# MiniAir724UG.net
KiCad netlist of a schematic drawn in Altium Designer
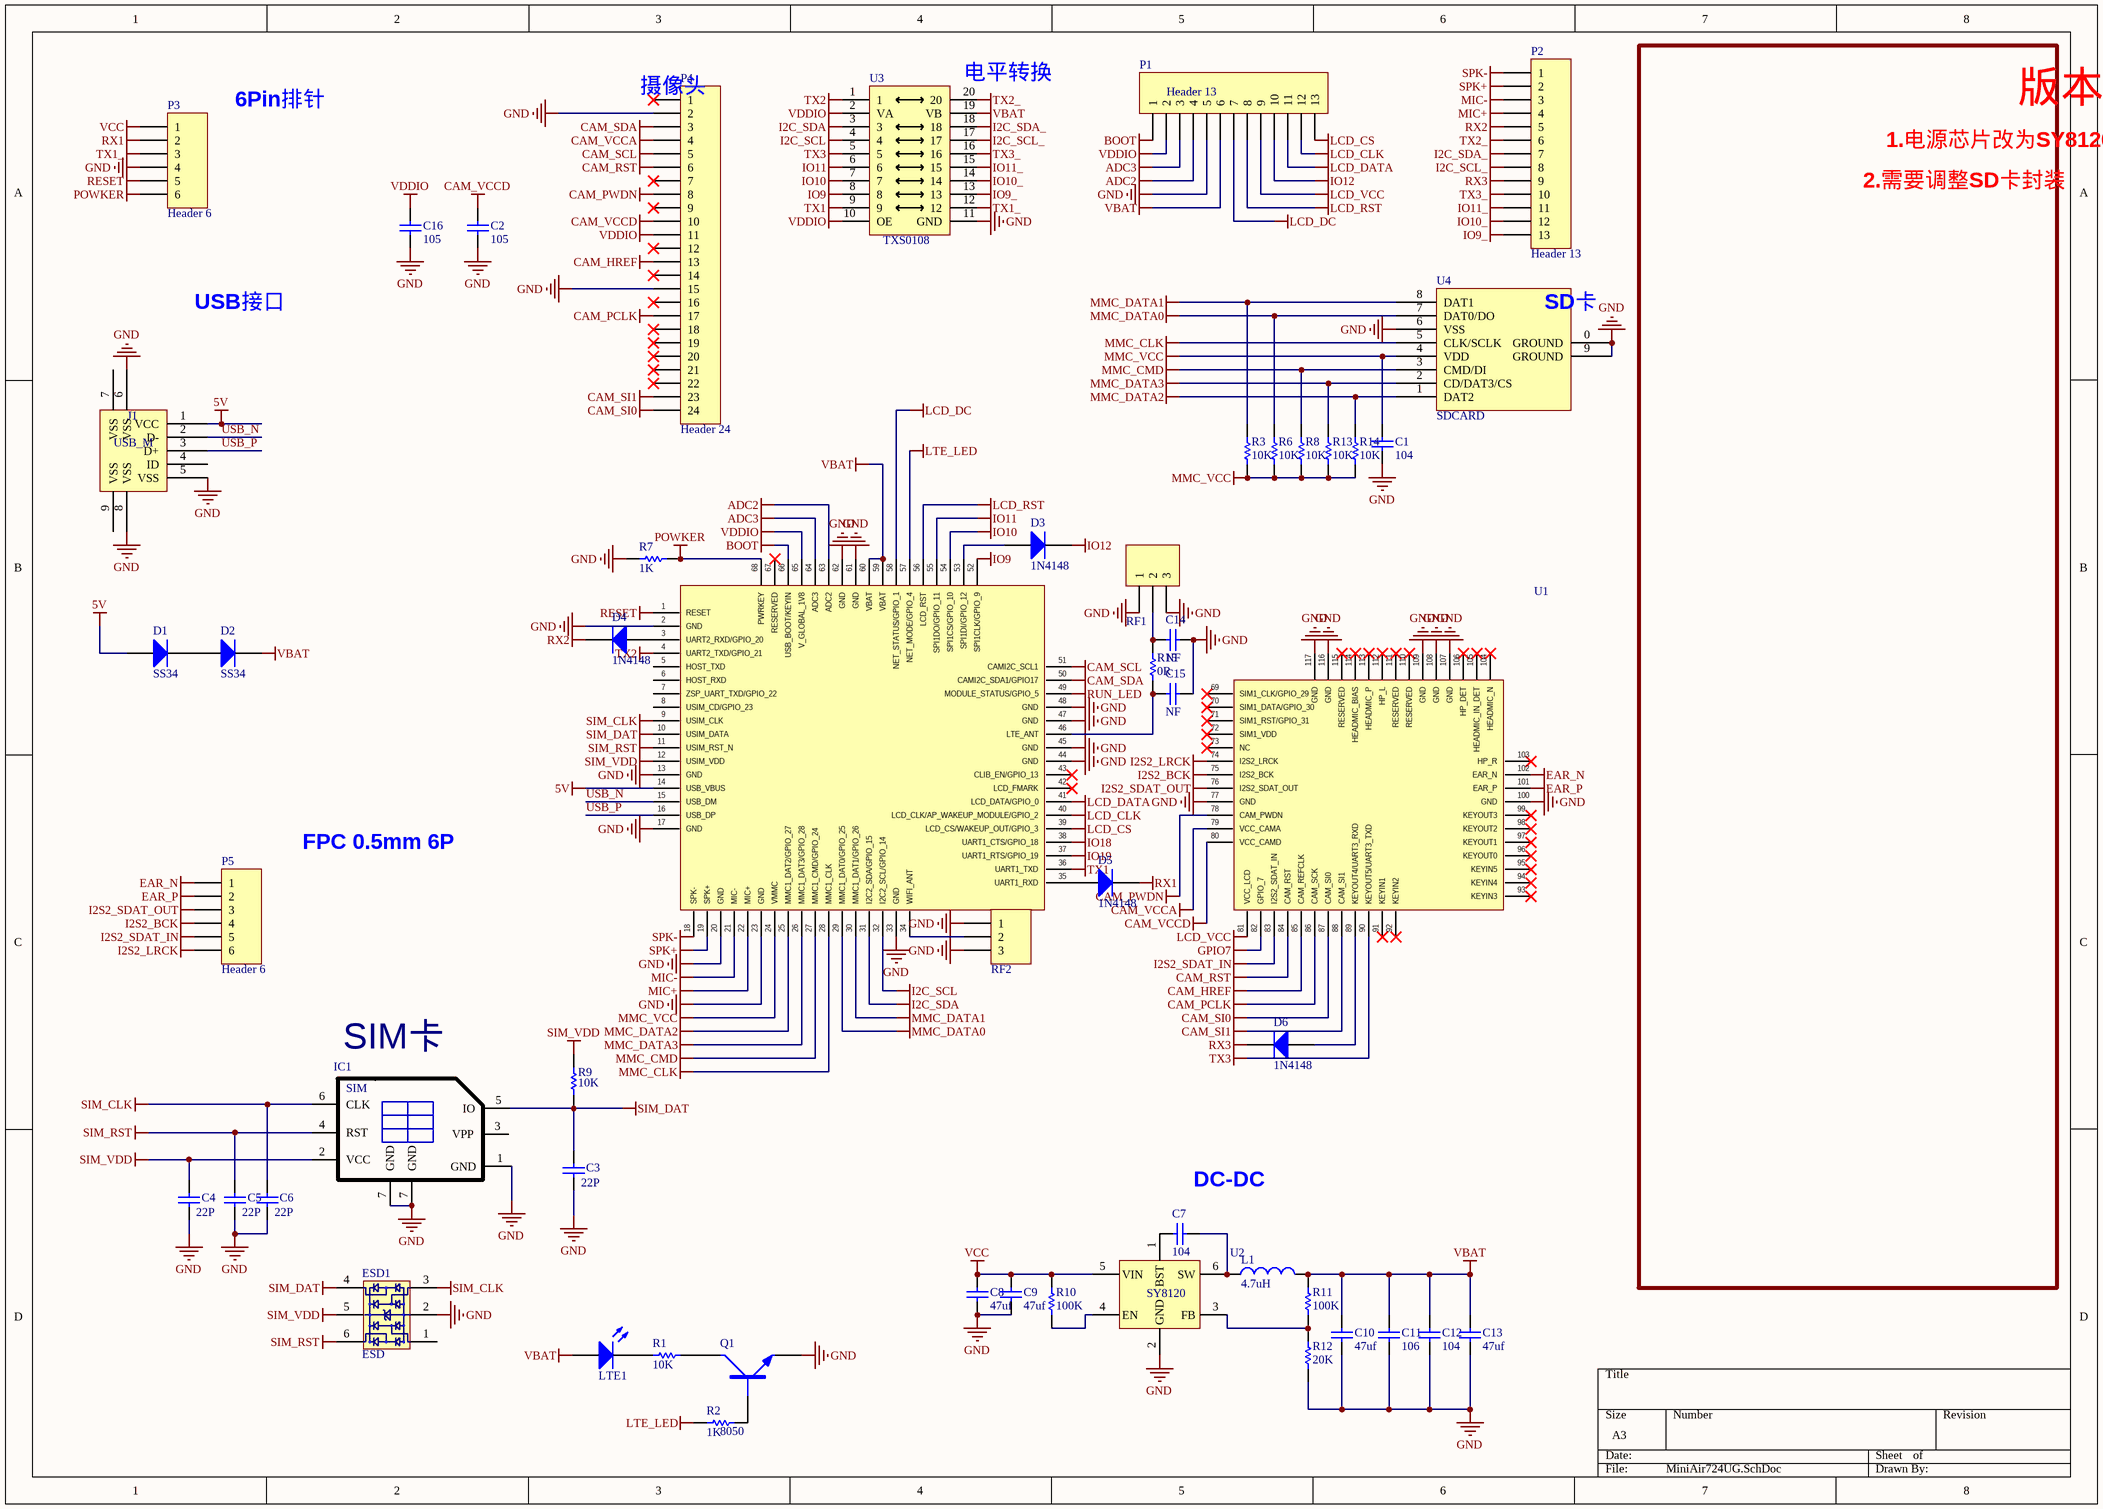
[diagram p0: MiniAir724UG.SchDoc]

(export (version "E")
  (design (tool "Eeschema 10.0.6"))
  (components
    (comp (ref "C1")
      (value "104")
      (footprint "0402C")
      (description "Capacitor")
      (fields (field (name "PUBLISHER") "Altium Limited"))
      (libsource (lib "Miscellaneous Devices") (part "Cap"))
    )
    (comp (ref "C2")
      (value "105")
      (footprint "0402C")
      (description "Capacitor")
      (fields (field (name "PUBLISHER") "Altium Limited"))
      (libsource (lib "Miscellaneous Devices") (part "Cap"))
    )
    (comp (ref "C3")
      (value "22P")
      (footprint "0402C")
      (description "Capacitor")
      (fields (field (name "PUBLISHER") "Altium Limited"))
      (libsource (lib "Miscellaneous Devices") (part "Cap"))
    )
    (comp (ref "C4")
      (value "22P")
      (footprint "0402C")
      (description "Capacitor")
      (fields (field (name "PUBLISHER") "Altium Limited"))
      (libsource (lib "Miscellaneous Devices") (part "Cap"))
    )
    (comp (ref "C5")
      (value "22P")
      (footprint "0402C")
      (description "Capacitor")
      (fields (field (name "PUBLISHER") "Altium Limited"))
      (libsource (lib "Miscellaneous Devices") (part "Cap"))
    )
    (comp (ref "C6")
      (value "22P")
      (footprint "0402C")
      (description "Capacitor")
      (fields (field (name "PUBLISHER") "Altium Limited"))
      (libsource (lib "Miscellaneous Devices") (part "Cap"))
    )
    (comp (ref "C7")
      (value "104")
      (footprint "0603C")
      (description "Capacitor")
      (fields (field (name "PUBLISHER") "Altium Limited"))
      (libsource (lib "Miscellaneous Devices") (part "Cap"))
    )
    (comp (ref "C8")
      (value "47uf")
      (footprint "1206C")
      (description "Capacitor")
      (fields (field (name "PUBLISHER") "Altium Limited"))
      (libsource (lib "Miscellaneous Devices") (part "Cap"))
    )
    (comp (ref "C9")
      (value "47uf")
      (footprint "1206C")
      (description "Capacitor")
      (fields (field (name "PUBLISHER") "Altium Limited"))
      (libsource (lib "Miscellaneous Devices") (part "Cap"))
    )
    (comp (ref "C10")
      (value "47uf")
      (footprint "1206C")
      (description "Capacitor")
      (fields (field (name "PUBLISHER") "Altium Limited"))
      (libsource (lib "Miscellaneous Devices") (part "Cap"))
    )
    (comp (ref "C11")
      (value "106")
      (footprint "0603C")
      (description "Capacitor")
      (fields (field (name "PUBLISHER") "Altium Limited"))
      (libsource (lib "Miscellaneous Devices") (part "Cap"))
    )
    (comp (ref "C12")
      (value "104")
      (footprint "0603C")
      (description "Capacitor")
      (fields (field (name "PUBLISHER") "Altium Limited"))
      (libsource (lib "Miscellaneous Devices") (part "Cap"))
    )
    (comp (ref "C13")
      (value "47uf")
      (footprint "1206C")
      (description "Capacitor")
      (fields (field (name "PUBLISHER") "Altium Limited"))
      (libsource (lib "Miscellaneous Devices") (part "Cap"))
    )
    (comp (ref "C14")
      (value "NF")
      (footprint "0603C")
      (description "Capacitor")
      (fields (field (name "PUBLISHER") "Altium Limited"))
      (libsource (lib "Miscellaneous Devices") (part "Cap"))
    )
    (comp (ref "C15")
      (value "NF")
      (footprint "0603C")
      (description "Capacitor")
      (fields (field (name "PUBLISHER") "Altium Limited"))
      (libsource (lib "Miscellaneous Devices") (part "Cap"))
    )
    (comp (ref "C16")
      (value "105")
      (footprint "0402C")
      (description "Capacitor")
      (fields (field (name "PUBLISHER") "Altium Limited"))
      (libsource (lib "Miscellaneous Devices") (part "Cap"))
    )
    (comp (ref "D1")
      (value "SS34")
      (footprint "SMA")
      (description "二极管")
      (fields (field (name "PUBLISHER") "Altium Limited"))
      (libsource (lib "Miscellaneous Devices") (part "Diode"))
    )
    (comp (ref "D2")
      (value "SS34")
      (footprint "SMA")
      (description "二极管")
      (fields (field (name "PUBLISHER") "Altium Limited"))
      (libsource (lib "Miscellaneous Devices") (part "Diode"))
    )
    (comp (ref "D3")
      (value "1N4148")
      (footprint "SOD-523")
      (description "快速二极管")
      (fields (field (name "PUBLISHER") "Altium Limited"))
      (libsource (lib "Miscellaneous Devices") (part "Diode"))
    )
    (comp (ref "D4")
      (value "1N4148")
      (footprint "SOD-523")
      (description "快速二极管")
      (fields (field (name "PUBLISHER") "Altium Limited"))
      (libsource (lib "Miscellaneous Devices") (part "Diode"))
    )
    (comp (ref "D5")
      (value "1N4148")
      (footprint "SOD-523")
      (description "快速二极管")
      (fields (field (name "PUBLISHER") "Altium Limited"))
      (libsource (lib "Miscellaneous Devices") (part "Diode"))
    )
    (comp (ref "D6")
      (value "1N4148")
      (footprint "SOD-523")
      (description "快速二极管")
      (fields (field (name "PUBLISHER") "Altium Limited"))
      (libsource (lib "Miscellaneous Devices") (part "Diode"))
    )
    (comp (ref "ESD1") (value "ESD") (footprint "PcbLib:SOT-236") (libsource (lib "fszhang") (part "ESD_4A")))
    (comp (ref "IC1") (value "SIM") (footprint "SIM-Nano") (libsource (lib "air202lib") (part "SIM")))
    (comp (ref "J1")
      (value "USB_M")
      (footprint "micro_usb_b")
      (description "MicroUSB接口")
      (libsource (lib "SchLib") (part "USB_M"))
    )
    (comp (ref "L1")
      (value "4.7uH")
      (footprint "SWPA4020S")
      (description "电感SLF7032")
      (fields (field (name "PUBLISHER") "Altium Limited"))
      (libsource (lib "Miscellaneous Devices") (part "Inductor"))
    )
    (comp (ref "LTE1")
      (value "LED")
      (footprint "0603LED")
      (description "Typical RED, GREEN, YELLOW, AMBER GaAs LED")
      (fields (field (name "PUBLISHER") "Altium Limited"))
      (libsource (lib "Miscellaneous Devices") (part "LED2"))
    )
    (comp (ref "P1")
      (value "Header 13")
      (footprint "HDR1X13")
      (description "Header, 13-Pin")
      (fields (field (name "PUBLISHER") "Altium Limited"))
      (libsource (lib "") (part "Header 13_1"))
    )
    (comp (ref "P2")
      (value "Header 13")
      (footprint "HDR1X13")
      (description "Header, 13-Pin")
      (fields (field (name "PUBLISHER") "Altium Limited"))
      (libsource (lib "Miscellaneous Connectors") (part "Header 13"))
    )
    (comp (ref "P3")
      (value "Header 6")
      (footprint "HDR1X6")
      (description "Header, 6-Pin")
      (fields (field (name "PUBLISHER") "Altium Limited"))
      (libsource (lib "Miscellaneous Connectors") (part "Header 6"))
    )
    (comp (ref "P4")
      (value "Header 24")
      (footprint "FPC0.5 2H-WS-24P")
      (description "Header, 24-Pin")
      (fields (field (name "PUBLISHER") "Altium Limited"))
      (libsource (lib "Miscellaneous Connectors") (part "Header 24"))
    )
    (comp (ref "P5")
      (value "Header 6")
      (footprint "FPC0.5 2H-WS-6P")
      (description "Header, 6-Pin")
      (fields (field (name "PUBLISHER") "Altium Limited"))
      (libsource (lib "Miscellaneous Connectors") (part "Header 6"))
    )
    (comp (ref "Q1") (value "8050") (footprint "SOT-23") (libsource (lib "32无线") (part "NPN")))
    (comp (ref "R1")
      (value "10K")
      (footprint "0402R")
      (description "Resistor")
      (fields (field (name "PUBLISHER") "Altium Limited"))
      (libsource (lib "Miscellaneous Devices") (part "Res1"))
    )
    (comp (ref "R2")
      (value "1K")
      (footprint "0402R")
      (description "Resistor")
      (fields (field (name "PUBLISHER") "Altium Limited"))
      (libsource (lib "Miscellaneous Devices") (part "Res1"))
    )
    (comp (ref "R3")
      (value "10K")
      (footprint "0402R")
      (description "Resistor")
      (fields (field (name "PUBLISHER") "Altium Limited"))
      (libsource (lib "Miscellaneous Devices") (part "Res1"))
    )
    (comp (ref "R6")
      (value "10K")
      (footprint "0402R")
      (description "Resistor")
      (fields (field (name "PUBLISHER") "Altium Limited"))
      (libsource (lib "Miscellaneous Devices") (part "Res1"))
    )
    (comp (ref "R7")
      (value "1K")
      (footprint "0402R")
      (description "Resistor")
      (fields (field (name "PUBLISHER") "Altium Limited"))
      (libsource (lib "Miscellaneous Devices") (part "Res1"))
    )
    (comp (ref "R8")
      (value "10K")
      (footprint "0402R")
      (description "Resistor")
      (fields (field (name "PUBLISHER") "Altium Limited"))
      (libsource (lib "Miscellaneous Devices") (part "Res1"))
    )
    (comp (ref "R9")
      (value "10K")
      (footprint "0402R")
      (description "Resistor")
      (fields (field (name "PUBLISHER") "Altium Limited"))
      (libsource (lib "Miscellaneous Devices") (part "Res1"))
    )
    (comp (ref "R10")
      (value "100K")
      (footprint "0603R")
      (description "Resistor")
      (fields (field (name "PUBLISHER") "Altium Limited"))
      (libsource (lib "Miscellaneous Devices") (part "Res1"))
    )
    (comp (ref "R11")
      (value "100K")
      (footprint "0603R")
      (description "Resistor")
      (fields (field (name "PUBLISHER") "Altium Limited"))
      (libsource (lib "Miscellaneous Devices") (part "Res1"))
    )
    (comp (ref "R12")
      (value "20K")
      (footprint "0603R")
      (description "Resistor")
      (fields (field (name "PUBLISHER") "Altium Limited"))
      (libsource (lib "Miscellaneous Devices") (part "Res1"))
    )
    (comp (ref "R13")
      (value "10K")
      (footprint "0402R")
      (description "Resistor")
      (fields (field (name "PUBLISHER") "Altium Limited"))
      (libsource (lib "Miscellaneous Devices") (part "Res1"))
    )
    (comp (ref "R14")
      (value "10K")
      (footprint "0402R")
      (description "Resistor")
      (fields (field (name "PUBLISHER") "Altium Limited"))
      (libsource (lib "Miscellaneous Devices") (part "Res1"))
    )
    (comp (ref "R15")
      (value "0R")
      (footprint "0603R")
      (description "Resistor")
      (fields (field (name "PUBLISHER") "Altium Limited"))
      (libsource (lib "Miscellaneous Devices") (part "Res1"))
    )
    (comp (ref "RF1")
      (value "Header 3")
      (footprint "IPEX")
      (description "接插件")
      (fields (field (name "PUBLISHER") "Altium Limited"))
      (libsource (lib "fszhang") (part "Header 3"))
    )
    (comp (ref "RF2")
      (value "Header 3")
      (footprint "IPEX")
      (description "接插件")
      (fields (field (name "PUBLISHER") "Altium Limited"))
      (libsource (lib "") (part "Header 3_1"))
    )
    (comp (ref "U1")
      (value "Air724")
      (footprint "AIR724UG")
      (fields (field (name "PUBLISHER") "Altium Limited"))
      (libsource (lib "SchLib") (part "Air724UG"))
    )
    (comp (ref "U2") (value "SY8120") (footprint "SOT-236") (libsource (lib "SchLib") (part "JW5026")))
    (comp (ref "U3") (value "TXS0108") (footprint "SSOP20") (libsource (lib "fszhang") (part "TXS0108")))
    (comp (ref "U4")
      (value "SDCARD")
      (footprint "SDCARD-Mini")
      (libsource (lib "SchLib") (part "SDCARD-Mini"))
    )
  )
  (nets
    (net (code "1") (name "/USB_N") (class "Default")
      (node (ref "J1") (pin "2") (pinfunction "D-_2") (pintype "passive"))
      (node (ref "U1") (pin "15") (pinfunction "USB_DM_15") (pintype "passive"))
    )
    (net (code "2") (name "/USB_P") (class "Default")
      (node (ref "J1") (pin "3") (pinfunction "D+_3") (pintype "passive"))
      (node (ref "U1") (pin "16") (pinfunction "USB_DP_16") (pintype "passive"))
    )
    (net (code "3") (name "5V") (class "Default")
      (node (ref "D1") (pin "1") (pinfunction "A_1") (pintype "passive"))
      (node (ref "J1") (pin "1") (pinfunction "VCC_1") (pintype "passive"))
      (node (ref "U1") (pin "14") (pinfunction "USB_VBUS_14") (pintype "passive"))
    )
    (net (code "4") (name "ADC2") (class "Default")
      (node (ref "P1") (pin "4") (pinfunction "4_4") (pintype "passive"))
      (node (ref "U1") (pin "63") (pinfunction "ADC2_63") (pintype "passive"))
    )
    (net (code "5") (name "ADC3") (class "Default")
      (node (ref "P1") (pin "3") (pinfunction "3_3") (pintype "passive"))
      (node (ref "U1") (pin "64") (pinfunction "ADC3_64") (pintype "passive"))
    )
    (net (code "6") (name "BOOT") (class "Default")
      (node (ref "P1") (pin "1") (pinfunction "1_1") (pintype "passive"))
      (node (ref "U1") (pin "66") (pinfunction "USB_BOOT/KEYIN_66") (pintype "passive"))
    )
    (net (code "7") (name "CAM_HREF") (class "Default")
      (node (ref "P4") (pin "13") (pinfunction "13_13") (pintype "passive"))
      (node (ref "U1") (pin "85") (pinfunction "CAM_REFCLK_85") (pintype "passive"))
    )
    (net (code "8") (name "CAM_PCLK") (class "Default")
      (node (ref "P4") (pin "17") (pinfunction "17_17") (pintype "passive"))
      (node (ref "U1") (pin "86") (pinfunction "CAM_SCK_86") (pintype "passive"))
    )
    (net (code "9") (name "CAM_PWDN") (class "Default")
      (node (ref "P4") (pin "8") (pinfunction "8_8") (pintype "passive"))
      (node (ref "U1") (pin "78") (pinfunction "CAM_PWDN_78") (pintype "passive"))
    )
    (net (code "10") (name "CAM_RST") (class "Default")
      (node (ref "P4") (pin "6") (pinfunction "6_6") (pintype "passive"))
      (node (ref "U1") (pin "84") (pinfunction "CAM_RST_84") (pintype "passive"))
    )
    (net (code "11") (name "CAM_SCL") (class "Default")
      (node (ref "P4") (pin "5") (pinfunction "5_5") (pintype "passive"))
      (node (ref "U1") (pin "51") (pinfunction "CAMI2C_SCL1_51") (pintype "passive"))
    )
    (net (code "12") (name "CAM_SDA") (class "Default")
      (node (ref "P4") (pin "3") (pinfunction "3_3") (pintype "passive"))
      (node (ref "U1") (pin "50") (pinfunction "CAMI2C_SDA1/GPIO17_50") (pintype "passive"))
    )
    (net (code "13") (name "CAM_SI0") (class "Default")
      (node (ref "P4") (pin "24") (pinfunction "24_24") (pintype "passive"))
      (node (ref "U1") (pin "87") (pinfunction "CAM_SI0_87") (pintype "passive"))
    )
    (net (code "14") (name "CAM_SI1") (class "Default")
      (node (ref "P4") (pin "23") (pinfunction "23_23") (pintype "passive"))
      (node (ref "U1") (pin "88") (pinfunction "CAM_SI1_88") (pintype "passive"))
    )
    (net (code "15") (name "CAM_VCCA") (class "Default")
      (node (ref "P4") (pin "4") (pinfunction "4_4") (pintype "passive"))
      (node (ref "U1") (pin "79") (pinfunction "VCC_CAMA_79") (pintype "passive"))
    )
    (net (code "16") (name "CAM_VCCD") (class "Default")
      (node (ref "C2") (pin "2") (pinfunction "2_2") (pintype "passive"))
      (node (ref "P4") (pin "10") (pinfunction "10_10") (pintype "passive"))
      (node (ref "U1") (pin "80") (pinfunction "VCC_CAMD_80") (pintype "passive"))
    )
    (net (code "17") (name "EAR_N") (class "Default")
      (node (ref "P5") (pin "1") (pinfunction "1_1") (pintype "passive"))
      (node (ref "U1") (pin "102") (pinfunction "EAR_N_102") (pintype "passive"))
    )
    (net (code "18") (name "EAR_P") (class "Default")
      (node (ref "P5") (pin "2") (pinfunction "2_2") (pintype "passive"))
      (node (ref "U1") (pin "101") (pinfunction "EAR_P_101") (pintype "passive"))
    )
    (net (code "19") (name "GND") (class "Default")
      (node (ref "C1") (pin "1") (pinfunction "1_1") (pintype "passive"))
      (node (ref "C10") (pin "1") (pinfunction "1_1") (pintype "passive"))
      (node (ref "C11") (pin "1") (pinfunction "1_1") (pintype "passive"))
      (node (ref "C12") (pin "1") (pinfunction "1_1") (pintype "passive"))
      (node (ref "C13") (pin "1") (pinfunction "1_1") (pintype "passive"))
      (node (ref "C14") (pin "1") (pinfunction "1_1") (pintype "passive"))
      (node (ref "C15") (pin "1") (pinfunction "1_1") (pintype "passive"))
      (node (ref "C16") (pin "1") (pinfunction "1_1") (pintype "passive"))
      (node (ref "C2") (pin "1") (pinfunction "1_1") (pintype "passive"))
      (node (ref "C3") (pin "2") (pinfunction "2_2") (pintype "passive"))
      (node (ref "C4") (pin "2") (pinfunction "2_2") (pintype "passive"))
      (node (ref "C5") (pin "2") (pinfunction "2_2") (pintype "passive"))
      (node (ref "C6") (pin "2") (pinfunction "2_2") (pintype "passive"))
      (node (ref "C8") (pin "1") (pinfunction "1_1") (pintype "passive"))
      (node (ref "C9") (pin "1") (pinfunction "1_1") (pintype "passive"))
      (node (ref "ESD1") (pin "2") (pinfunction "2_2") (pintype "passive"))
      (node (ref "IC1") (pin "1") (pinfunction "GND_1") (pintype "passive"))
      (node (ref "IC1") (pin "7") (pinfunction "GND_7") (pintype "passive"))
      (node (ref "J1") (pin "5") (pinfunction "VSS_5") (pintype "passive"))
      (node (ref "J1") (pin "6") (pinfunction "VSS_6") (pintype "passive"))
      (node (ref "J1") (pin "8") (pinfunction "VSS_8") (pintype "passive"))
      (node (ref "P1") (pin "5") (pinfunction "5_5") (pintype "passive"))
      (node (ref "P3") (pin "4") (pinfunction "4_4") (pintype "passive"))
      (node (ref "P4") (pin "15") (pinfunction "15_15") (pintype "passive"))
      (node (ref "P4") (pin "2") (pinfunction "2_2") (pintype "passive"))
      (node (ref "Q1") (pin "2") (pinfunction "E_2") (pintype "passive"))
      (node (ref "R12") (pin "1") (pinfunction "1_1") (pintype "passive"))
      (node (ref "R7") (pin "1") (pinfunction "1_1") (pintype "passive"))
      (node (ref "RF1") (pin "1") (pinfunction "1_1") (pintype "passive"))
      (node (ref "RF1") (pin "3") (pinfunction "3_3") (pintype "passive"))
      (node (ref "RF2") (pin "1") (pinfunction "1_1") (pintype "passive"))
      (node (ref "RF2") (pin "3") (pinfunction "3_3") (pintype "passive"))
      (node (ref "U1") (pin "100") (pinfunction "GND_100") (pintype "passive"))
      (node (ref "U1") (pin "107") (pinfunction "GND_107") (pintype "passive"))
      (node (ref "U1") (pin "108") (pinfunction "GND_108") (pintype "passive"))
      (node (ref "U1") (pin "109") (pinfunction "GND_109") (pintype "passive"))
      (node (ref "U1") (pin "116") (pinfunction "GND_116") (pintype "passive"))
      (node (ref "U1") (pin "117") (pinfunction "GND_117") (pintype "passive"))
      (node (ref "U1") (pin "13") (pinfunction "GND_13") (pintype "passive"))
      (node (ref "U1") (pin "17") (pinfunction "GND_17") (pintype "passive"))
      (node (ref "U1") (pin "2") (pinfunction "GND_2") (pintype "passive"))
      (node (ref "U1") (pin "20") (pinfunction "GND_20") (pintype "passive"))
      (node (ref "U1") (pin "23") (pinfunction "GND_23") (pintype "passive"))
      (node (ref "U1") (pin "33") (pinfunction "GND_33") (pintype "passive"))
      (node (ref "U1") (pin "44") (pinfunction "GND_44") (pintype "passive"))
      (node (ref "U1") (pin "45") (pinfunction "GND_45") (pintype "passive"))
      (node (ref "U1") (pin "47") (pinfunction "GND_47") (pintype "passive"))
      (node (ref "U1") (pin "48") (pinfunction "GND_48") (pintype "passive"))
      (node (ref "U1") (pin "61") (pinfunction "GND_61") (pintype "passive"))
      (node (ref "U1") (pin "62") (pinfunction "GND_62") (pintype "passive"))
      (node (ref "U1") (pin "77") (pinfunction "GND_77") (pintype "passive"))
      (node (ref "U2") (pin "2") (pinfunction "GND_2") (pintype "passive"))
      (node (ref "U3") (pin "11") (pinfunction "GND_11") (pintype "passive"))
      (node (ref "U4") (pin "0") (pinfunction "GROUND_0") (pintype "passive"))
      (node (ref "U4") (pin "6") (pinfunction "VSS_6") (pintype "passive"))
      (node (ref "U4") (pin "9") (pinfunction "GROUND_9") (pintype "passive"))
    )
    (net (code "20") (name "GPIO7") (class "Default")
      (node (ref "U1") (pin "82") (pinfunction "GPIO_7_82") (pintype "passive"))
    )
    (net (code "21") (name "I2C_SCL") (class "Default")
      (node (ref "U1") (pin "32") (pinfunction "I2C2_SCL/GPIO_14_32") (pintype "passive"))
      (node (ref "U3") (pin "4") (pinfunction "4_4") (pintype "passive"))
    )
    (net (code "22") (name "I2C_SCL_") (class "Default")
      (node (ref "P2") (pin "8") (pinfunction "8_8") (pintype "passive"))
      (node (ref "U3") (pin "17") (pinfunction "17_17") (pintype "passive"))
    )
    (net (code "23") (name "I2C_SDA") (class "Default")
      (node (ref "U1") (pin "31") (pinfunction "I2C2_SDA/GPIO_15_31") (pintype "passive"))
      (node (ref "U3") (pin "3") (pinfunction "3_3") (pintype "passive"))
    )
    (net (code "24") (name "I2C_SDA_") (class "Default")
      (node (ref "P2") (pin "7") (pinfunction "7_7") (pintype "passive"))
      (node (ref "U3") (pin "18") (pinfunction "18_18") (pintype "passive"))
    )
    (net (code "25") (name "I2S2_BCK") (class "Default")
      (node (ref "P5") (pin "4") (pinfunction "4_4") (pintype "passive"))
      (node (ref "U1") (pin "75") (pinfunction "I2S2_BCK_75") (pintype "passive"))
    )
    (net (code "26") (name "I2S2_LRCK") (class "Default")
      (node (ref "P5") (pin "6") (pinfunction "6_6") (pintype "passive"))
      (node (ref "U1") (pin "74") (pinfunction "I2S2_LRCK_74") (pintype "passive"))
    )
    (net (code "27") (name "I2S2_SDAT_IN") (class "Default")
      (node (ref "P5") (pin "5") (pinfunction "5_5") (pintype "passive"))
      (node (ref "U1") (pin "83") (pinfunction "I2S2_SDAT_IN_83") (pintype "passive"))
    )
    (net (code "28") (name "I2S2_SDAT_OUT") (class "Default")
      (node (ref "P5") (pin "3") (pinfunction "3_3") (pintype "passive"))
      (node (ref "U1") (pin "76") (pinfunction "I2S2_SDAT_OUT_76") (pintype "passive"))
    )
    (net (code "29") (name "IO9") (class "Default")
      (node (ref "U1") (pin "52") (pinfunction "SPI1CLK/GPIO_9_52") (pintype "passive"))
      (node (ref "U3") (pin "8") (pinfunction "8_8") (pintype "passive"))
    )
    (net (code "30") (name "IO9_") (class "Default")
      (node (ref "P2") (pin "13") (pinfunction "13_13") (pintype "passive"))
      (node (ref "U3") (pin "13") (pinfunction "13_13") (pintype "passive"))
    )
    (net (code "31") (name "IO10") (class "Default")
      (node (ref "U1") (pin "54") (pinfunction "SPI1CS/GPIO_10_54") (pintype "passive"))
      (node (ref "U3") (pin "7") (pinfunction "7_7") (pintype "passive"))
    )
    (net (code "32") (name "IO10_") (class "Default")
      (node (ref "P2") (pin "12") (pinfunction "12_12") (pintype "passive"))
      (node (ref "U3") (pin "14") (pinfunction "14_14") (pintype "passive"))
    )
    (net (code "33") (name "IO11") (class "Default")
      (node (ref "U1") (pin "55") (pinfunction "SPI1DO/GPIO_11_55") (pintype "passive"))
      (node (ref "U3") (pin "6") (pinfunction "6_6") (pintype "passive"))
    )
    (net (code "34") (name "IO11_") (class "Default")
      (node (ref "P2") (pin "11") (pinfunction "11_11") (pintype "passive"))
      (node (ref "U3") (pin "15") (pinfunction "15_15") (pintype "passive"))
    )
    (net (code "35") (name "IO12") (class "Default")
      (node (ref "D3") (pin "2") (pinfunction "K_2") (pintype "passive"))
      (node (ref "P1") (pin "10") (pinfunction "10_10") (pintype "passive"))
    )
    (net (code "36") (name "IO18") (class "Default")
      (node (ref "U1") (pin "38") (pinfunction "UART1_CTS/GPIO_18_38") (pintype "passive"))
    )
    (net (code "37") (name "IO19") (class "Default")
      (node (ref "U1") (pin "37") (pinfunction "UART1_RTS/GPIO_19_37") (pintype "passive"))
    )
    (net (code "38") (name "LCD_CLK") (class "Default")
      (node (ref "P1") (pin "12") (pinfunction "12_12") (pintype "passive"))
      (node (ref "U1") (pin "40") (pinfunction "LCD_CLK/AP_WAKEUP_MODULE/GPIO_2_40") (pintype "passive"))
    )
    (net (code "39") (name "LCD_CS") (class "Default")
      (node (ref "P1") (pin "13") (pinfunction "13_13") (pintype "passive"))
      (node (ref "U1") (pin "39") (pinfunction "LCD_CS/WAKEUP_OUT/GPIO_3_39") (pintype "passive"))
    )
    (net (code "40") (name "LCD_DATA") (class "Default")
      (node (ref "P1") (pin "11") (pinfunction "11_11") (pintype "passive"))
      (node (ref "U1") (pin "41") (pinfunction "LCD_DATA/GPIO_0_41") (pintype "passive"))
    )
    (net (code "41") (name "LCD_DC") (class "Default")
      (node (ref "P1") (pin "7") (pinfunction "7_7") (pintype "passive"))
      (node (ref "U1") (pin "58") (pinfunction "NET_STATUS/GPIO_1_58") (pintype "passive"))
    )
    (net (code "42") (name "LCD_RST") (class "Default")
      (node (ref "P1") (pin "8") (pinfunction "8_8") (pintype "passive"))
      (node (ref "U1") (pin "56") (pinfunction "LCD_RST_56") (pintype "passive"))
    )
    (net (code "43") (name "LCD_VCC") (class "Default")
      (node (ref "P1") (pin "9") (pinfunction "9_9") (pintype "passive"))
      (node (ref "U1") (pin "81") (pinfunction "VCC_LCD_81") (pintype "passive"))
    )
    (net (code "44") (name "LTE_LED") (class "Default")
      (node (ref "R2") (pin "2") (pinfunction "2_2") (pintype "passive"))
      (node (ref "U1") (pin "57") (pinfunction "NET_MODE/GPIO_4_57") (pintype "passive"))
    )
    (net (code "45") (name "MIC+") (class "Default")
      (node (ref "P2") (pin "4") (pinfunction "4_4") (pintype "passive"))
      (node (ref "U1") (pin "22") (pinfunction "MIC+_22") (pintype "passive"))
    )
    (net (code "46") (name "MIC-") (class "Default")
      (node (ref "P2") (pin "3") (pinfunction "3_3") (pintype "passive"))
      (node (ref "U1") (pin "21") (pinfunction "MIC-_21") (pintype "passive"))
    )
    (net (code "47") (name "MMC_CLK") (class "Default")
      (node (ref "U1") (pin "28") (pinfunction "MMC1_CLK_28") (pintype "passive"))
      (node (ref "U4") (pin "5") (pinfunction "CLK/SCLK_5") (pintype "passive"))
    )
    (net (code "48") (name "MMC_CMD") (class "Default")
      (node (ref "R8") (pin "1") (pinfunction "1_1") (pintype "passive"))
      (node (ref "U1") (pin "27") (pinfunction "MMC1_CMD/GPIO_24_27") (pintype "passive"))
      (node (ref "U4") (pin "3") (pinfunction "CMD/DI_3") (pintype "passive"))
    )
    (net (code "49") (name "MMC_DATA0") (class "Default")
      (node (ref "R6") (pin "1") (pinfunction "1_1") (pintype "passive"))
      (node (ref "U1") (pin "29") (pinfunction "MMC1_DAT0/GPIO_25_29") (pintype "passive"))
      (node (ref "U4") (pin "7") (pinfunction "DAT0/DO_7") (pintype "passive"))
    )
    (net (code "50") (name "MMC_DATA1") (class "Default")
      (node (ref "R3") (pin "1") (pinfunction "1_1") (pintype "passive"))
      (node (ref "U1") (pin "30") (pinfunction "MMC1_DAT1/GPIO_26_30") (pintype "passive"))
      (node (ref "U4") (pin "8") (pinfunction "DAT1_8") (pintype "passive"))
    )
    (net (code "51") (name "MMC_DATA2") (class "Default")
      (node (ref "R14") (pin "1") (pinfunction "1_1") (pintype "passive"))
      (node (ref "U1") (pin "25") (pinfunction "MMC1_DAT2/GPIO_27_25") (pintype "passive"))
      (node (ref "U4") (pin "1") (pinfunction "DAT2_1") (pintype "passive"))
    )
    (net (code "52") (name "MMC_DATA3") (class "Default")
      (node (ref "R13") (pin "1") (pinfunction "1_1") (pintype "passive"))
      (node (ref "U1") (pin "26") (pinfunction "MMC1_DAT3/GPIO_28_26") (pintype "passive"))
      (node (ref "U4") (pin "2") (pinfunction "CD/DAT3/CS_2") (pintype "passive"))
    )
    (net (code "53") (name "MMC_VCC") (class "Default")
      (node (ref "C1") (pin "2") (pinfunction "2_2") (pintype "passive"))
      (node (ref "R13") (pin "2") (pinfunction "2_2") (pintype "passive"))
      (node (ref "R14") (pin "2") (pinfunction "2_2") (pintype "passive"))
      (node (ref "R3") (pin "2") (pinfunction "2_2") (pintype "passive"))
      (node (ref "R6") (pin "2") (pinfunction "2_2") (pintype "passive"))
      (node (ref "R8") (pin "2") (pinfunction "2_2") (pintype "passive"))
      (node (ref "U1") (pin "24") (pinfunction "VMMC_24") (pintype "passive"))
      (node (ref "U4") (pin "4") (pinfunction "VDD_4") (pintype "passive"))
    )
    (net (code "54") (name "Net-(C14-Pad2)") (class "Default")
      (node (ref "C14") (pin "2") (pinfunction "2_2") (pintype "passive"))
      (node (ref "R15") (pin "2") (pinfunction "2_2") (pintype "passive"))
      (node (ref "RF1") (pin "2") (pinfunction "2_2") (pintype "passive"))
    )
    (net (code "55") (name "Net-(D1-K)") (class "Default")
      (node (ref "D1") (pin "2") (pinfunction "K_2") (pintype "passive"))
      (node (ref "D2") (pin "1") (pinfunction "A_1") (pintype "passive"))
    )
    (net (code "56") (name "Net-(D3-A)") (class "Default")
      (node (ref "D3") (pin "1") (pinfunction "A_1") (pintype "passive"))
      (node (ref "U1") (pin "53") (pinfunction "SPI1DI/GPIO_12_53") (pintype "passive"))
    )
    (net (code "57") (name "Net-(D4-A)") (class "Default")
      (node (ref "D4") (pin "1") (pinfunction "A_1") (pintype "passive"))
      (node (ref "U1") (pin "3") (pinfunction "UART2_RXD/GPIO_20_3") (pintype "passive"))
    )
    (net (code "58") (name "Net-(D5-A)") (class "Default")
      (node (ref "D5") (pin "1") (pinfunction "A_1") (pintype "passive"))
      (node (ref "U1") (pin "35") (pinfunction "UART1_RXD_35") (pintype "passive"))
    )
    (net (code "59") (name "Net-(D6-A)") (class "Default")
      (node (ref "D6") (pin "1") (pinfunction "A_1") (pintype "passive"))
      (node (ref "U1") (pin "89") (pinfunction "KEYOUT4/UART3_RXD_89") (pintype "passive"))
    )
    (net (code "60") (name "Net-(LTE1-K)") (class "Default")
      (node (ref "LTE1") (pin "2") (pinfunction "K_2") (pintype "passive"))
      (node (ref "R1") (pin "2") (pinfunction "2_2") (pintype "passive"))
    )
    (net (code "61") (name "Net-(Q1-B)") (class "Default")
      (node (ref "Q1") (pin "1") (pinfunction "B_1") (pintype "passive"))
      (node (ref "R2") (pin "1") (pinfunction "1_1") (pintype "passive"))
    )
    (net (code "62") (name "Net-(Q1-C)") (class "Default")
      (node (ref "Q1") (pin "3") (pinfunction "C_3") (pintype "passive"))
      (node (ref "R1") (pin "1") (pinfunction "1_1") (pintype "passive"))
    )
    (net (code "63") (name "Net-(U1-LTE_ANT)") (class "Default")
      (node (ref "C15") (pin "2") (pinfunction "2_2") (pintype "passive"))
      (node (ref "R15") (pin "1") (pinfunction "1_1") (pintype "passive"))
      (node (ref "U1") (pin "46") (pinfunction "LTE_ANT_46") (pintype "passive"))
    )
    (net (code "64") (name "Net-(U1-WIFI_ANT)") (class "Default")
      (node (ref "RF2") (pin "2") (pinfunction "2_2") (pintype "passive"))
      (node (ref "U1") (pin "34") (pinfunction "WIFI_ANT_34") (pintype "passive"))
    )
    (net (code "65") (name "Net-(U2-BST)") (class "Default")
      (node (ref "C7") (pin "1") (pinfunction "1_1") (pintype "passive"))
      (node (ref "U2") (pin "1") (pinfunction "BST_1") (pintype "passive"))
    )
    (net (code "66") (name "Net-(U2-EN)") (class "Default")
      (node (ref "R10") (pin "2") (pinfunction "2_2") (pintype "passive"))
      (node (ref "U2") (pin "4") (pinfunction "EN_4") (pintype "passive"))
    )
    (net (code "67") (name "Net-(U2-FB)") (class "Default")
      (node (ref "R11") (pin "1") (pinfunction "1_1") (pintype "passive"))
      (node (ref "R12") (pin "2") (pinfunction "2_2") (pintype "passive"))
      (node (ref "U2") (pin "3") (pinfunction "FB_3") (pintype "passive"))
    )
    (net (code "68") (name "Net-(U2-SW)") (class "Default")
      (node (ref "C7") (pin "2") (pinfunction "2_2") (pintype "passive"))
      (node (ref "L1") (pin "1") (pinfunction "1_1") (pintype "passive"))
      (node (ref "U2") (pin "6") (pinfunction "SW_6") (pintype "passive"))
    )
    (net (code "69") (name "POWKER") (class "Default")
      (node (ref "P3") (pin "6") (pinfunction "6_6") (pintype "passive"))
      (node (ref "R7") (pin "2") (pinfunction "2_2") (pintype "passive"))
      (node (ref "U1") (pin "68") (pinfunction "PWRKEY_68") (pintype "passive"))
    )
    (net (code "70") (name "RESET") (class "Default")
      (node (ref "P3") (pin "5") (pinfunction "5_5") (pintype "passive"))
      (node (ref "U1") (pin "1") (pinfunction "RESET_1") (pintype "passive"))
    )
    (net (code "71") (name "RUN_LED") (class "Default")
      (node (ref "U1") (pin "49") (pinfunction "MODULE_STATUS/GPIO_5_49") (pintype "passive"))
    )
    (net (code "72") (name "RX1") (class "Default")
      (node (ref "D5") (pin "2") (pinfunction "K_2") (pintype "passive"))
      (node (ref "P3") (pin "2") (pinfunction "2_2") (pintype "passive"))
    )
    (net (code "73") (name "RX2") (class "Default")
      (node (ref "D4") (pin "2") (pinfunction "K_2") (pintype "passive"))
      (node (ref "P2") (pin "5") (pinfunction "5_5") (pintype "passive"))
    )
    (net (code "74") (name "RX3") (class "Default")
      (node (ref "D6") (pin "2") (pinfunction "K_2") (pintype "passive"))
      (node (ref "P2") (pin "9") (pinfunction "9_9") (pintype "passive"))
    )
    (net (code "75") (name "SIM_CLK") (class "Default")
      (node (ref "C6") (pin "1") (pinfunction "1_1") (pintype "passive"))
      (node (ref "ESD1") (pin "3") (pinfunction "3_3") (pintype "passive"))
      (node (ref "IC1") (pin "6") (pinfunction "CLK_6") (pintype "passive"))
      (node (ref "U1") (pin "9") (pinfunction "USIM_CLK_9") (pintype "passive"))
    )
    (net (code "76") (name "SIM_DAT") (class "Default")
      (node (ref "C3") (pin "1") (pinfunction "1_1") (pintype "passive"))
      (node (ref "ESD1") (pin "4") (pinfunction "4_4") (pintype "passive"))
      (node (ref "IC1") (pin "5") (pinfunction "IO_5") (pintype "passive"))
      (node (ref "R9") (pin "2") (pinfunction "2_2") (pintype "passive"))
      (node (ref "U1") (pin "10") (pinfunction "USIM_DATA_10") (pintype "passive"))
    )
    (net (code "77") (name "SIM_RST") (class "Default")
      (node (ref "C5") (pin "1") (pinfunction "1_1") (pintype "passive"))
      (node (ref "ESD1") (pin "6") (pinfunction "6_6") (pintype "passive"))
      (node (ref "IC1") (pin "4") (pinfunction "RST_4") (pintype "passive"))
      (node (ref "U1") (pin "11") (pinfunction "USIM_RST_N_11") (pintype "passive"))
    )
    (net (code "78") (name "SIM_VDD") (class "Default")
      (node (ref "C4") (pin "1") (pinfunction "1_1") (pintype "passive"))
      (node (ref "ESD1") (pin "5") (pinfunction "5_5") (pintype "passive"))
      (node (ref "IC1") (pin "2") (pinfunction "VCC_2") (pintype "passive"))
      (node (ref "R9") (pin "1") (pinfunction "1_1") (pintype "passive"))
      (node (ref "U1") (pin "12") (pinfunction "USIM_VDD_12") (pintype "passive"))
    )
    (net (code "79") (name "SPK+") (class "Default")
      (node (ref "P2") (pin "2") (pinfunction "2_2") (pintype "passive"))
      (node (ref "U1") (pin "19") (pinfunction "SPK+_19") (pintype "passive"))
    )
    (net (code "80") (name "SPK-") (class "Default")
      (node (ref "P2") (pin "1") (pinfunction "1_1") (pintype "passive"))
      (node (ref "U1") (pin "18") (pinfunction "SPK-_18") (pintype "passive"))
    )
    (net (code "81") (name "TX1") (class "Default")
      (node (ref "U1") (pin "36") (pinfunction "UART1_TXD_36") (pintype "passive"))
      (node (ref "U3") (pin "9") (pinfunction "9_9") (pintype "passive"))
    )
    (net (code "82") (name "TX1_") (class "Default")
      (node (ref "P3") (pin "3") (pinfunction "3_3") (pintype "passive"))
      (node (ref "U3") (pin "12") (pinfunction "12_12") (pintype "passive"))
    )
    (net (code "83") (name "TX2") (class "Default")
      (node (ref "U1") (pin "4") (pinfunction "UART2_TXD/GPIO_21_4") (pintype "passive"))
      (node (ref "U3") (pin "1") (pinfunction "1_1") (pintype "power_in"))
    )
    (net (code "84") (name "TX2_") (class "Default")
      (node (ref "P2") (pin "6") (pinfunction "6_6") (pintype "passive"))
      (node (ref "U3") (pin "20") (pinfunction "20_20") (pintype "passive"))
    )
    (net (code "85") (name "TX3") (class "Default")
      (node (ref "U1") (pin "90") (pinfunction "KEYOUT5/UART3_TXD_90") (pintype "passive"))
      (node (ref "U3") (pin "5") (pinfunction "5_5") (pintype "passive"))
    )
    (net (code "86") (name "TX3_") (class "Default")
      (node (ref "P2") (pin "10") (pinfunction "10_10") (pintype "passive"))
      (node (ref "U3") (pin "16") (pinfunction "16_16") (pintype "passive"))
    )
    (net (code "87") (name "VBAT") (class "Default")
      (node (ref "C10") (pin "2") (pinfunction "2_2") (pintype "passive"))
      (node (ref "C11") (pin "2") (pinfunction "2_2") (pintype "passive"))
      (node (ref "C12") (pin "2") (pinfunction "2_2") (pintype "passive"))
      (node (ref "C13") (pin "2") (pinfunction "2_2") (pintype "passive"))
      (node (ref "D2") (pin "2") (pinfunction "K_2") (pintype "passive"))
      (node (ref "L1") (pin "2") (pinfunction "2_2") (pintype "passive"))
      (node (ref "LTE1") (pin "1") (pinfunction "A_1") (pintype "passive"))
      (node (ref "P1") (pin "6") (pinfunction "6_6") (pintype "passive"))
      (node (ref "R11") (pin "2") (pinfunction "2_2") (pintype "passive"))
      (node (ref "U1") (pin "59") (pinfunction "VBAT_59") (pintype "passive"))
      (node (ref "U1") (pin "60") (pinfunction "VBAT_60") (pintype "passive"))
      (node (ref "U3") (pin "19") (pinfunction "VB_19") (pintype "passive"))
    )
    (net (code "88") (name "VCC") (class "Default")
      (node (ref "C8") (pin "2") (pinfunction "2_2") (pintype "passive"))
      (node (ref "C9") (pin "2") (pinfunction "2_2") (pintype "passive"))
      (node (ref "P3") (pin "1") (pinfunction "1_1") (pintype "passive"))
      (node (ref "R10") (pin "1") (pinfunction "1_1") (pintype "passive"))
      (node (ref "U2") (pin "5") (pinfunction "VIN_5") (pintype "passive"))
    )
    (net (code "89") (name "VDDIO") (class "Default")
      (node (ref "C16") (pin "2") (pinfunction "2_2") (pintype "passive"))
      (node (ref "P1") (pin "2") (pinfunction "2_2") (pintype "passive"))
      (node (ref "P4") (pin "11") (pinfunction "11_11") (pintype "passive"))
      (node (ref "U1") (pin "65") (pinfunction "V_GLOBAL_1V8_65") (pintype "passive"))
      (node (ref "U3") (pin "10") (pinfunction "OE_10") (pintype "passive"))
      (node (ref "U3") (pin "2") (pinfunction "VA_2") (pintype "passive"))
    )
    (net (code "90") (name "unconnected-(ESD1-Pad1)") (class "Default")
      (node (ref "ESD1") (pin "1") (pinfunction "1_1") (pintype "passive"))
    )
    (net (code "91") (name "unconnected-(IC1-VPP-Pad3)") (class "Default")
      (node (ref "IC1") (pin "3") (pinfunction "VPP_3") (pintype "passive"))
    )
    (net (code "92") (name "unconnected-(J1-ID-Pad4)") (class "Default")
      (node (ref "J1") (pin "4") (pinfunction "ID_4") (pintype "passive"))
    )
    (net (code "93") (name "unconnected-(J1-VSS-Pad7)") (class "Default")
      (node (ref "J1") (pin "7") (pinfunction "VSS_7") (pintype "passive"))
    )
    (net (code "94") (name "unconnected-(J1-VSS-Pad9)") (class "Default")
      (node (ref "J1") (pin "9") (pinfunction "VSS_9") (pintype "passive"))
    )
    (net (code "95") (name "unconnected-(P4-Pad1)") (class "Default")
      (node (ref "P4") (pin "1") (pinfunction "1_1") (pintype "passive+no_connect"))
    )
    (net (code "96") (name "unconnected-(P4-Pad7)") (class "Default")
      (node (ref "P4") (pin "7") (pinfunction "7_7") (pintype "passive+no_connect"))
    )
    (net (code "97") (name "unconnected-(P4-Pad9)") (class "Default")
      (node (ref "P4") (pin "9") (pinfunction "9_9") (pintype "passive+no_connect"))
    )
    (net (code "98") (name "unconnected-(P4-Pad12)") (class "Default")
      (node (ref "P4") (pin "12") (pinfunction "12_12") (pintype "passive+no_connect"))
    )
    (net (code "99") (name "unconnected-(P4-Pad14)") (class "Default")
      (node (ref "P4") (pin "14") (pinfunction "14_14") (pintype "passive+no_connect"))
    )
    (net (code "100") (name "unconnected-(P4-Pad16)") (class "Default")
      (node (ref "P4") (pin "16") (pinfunction "16_16") (pintype "passive+no_connect"))
    )
    (net (code "101") (name "unconnected-(P4-Pad18)") (class "Default")
      (node (ref "P4") (pin "18") (pinfunction "18_18") (pintype "passive+no_connect"))
    )
    (net (code "102") (name "unconnected-(P4-Pad19)") (class "Default")
      (node (ref "P4") (pin "19") (pinfunction "19_19") (pintype "passive+no_connect"))
    )
    (net (code "103") (name "unconnected-(P4-Pad20)") (class "Default")
      (node (ref "P4") (pin "20") (pinfunction "20_20") (pintype "passive+no_connect"))
    )
    (net (code "104") (name "unconnected-(P4-Pad21)") (class "Default")
      (node (ref "P4") (pin "21") (pinfunction "21_21") (pintype "passive+no_connect"))
    )
    (net (code "105") (name "unconnected-(P4-Pad22)") (class "Default")
      (node (ref "P4") (pin "22") (pinfunction "22_22") (pintype "passive+no_connect"))
    )
    (net (code "106") (name "unconnected-(U1-CLIB_EN{slash}GPIO_13-Pad43)") (class "Default")
      (node (ref "U1") (pin "43") (pinfunction "CLIB_EN/GPIO_13_43") (pintype "passive+no_connect"))
    )
    (net (code "107") (name "unconnected-(U1-HEADMIC_BIAS-Pad114)") (class "Default")
      (node (ref "U1") (pin "114") (pinfunction "HEADMIC_BIAS_114") (pintype "passive+no_connect"))
    )
    (net (code "108") (name "unconnected-(U1-HEADMIC_IN_DET-Pad105)") (class "Default")
      (node (ref "U1") (pin "105") (pinfunction "HEADMIC_IN_DET_105") (pintype "passive+no_connect"))
    )
    (net (code "109") (name "unconnected-(U1-HEADMIC_N-Pad104)") (class "Default")
      (node (ref "U1") (pin "104") (pinfunction "HEADMIC_N_104") (pintype "passive+no_connect"))
    )
    (net (code "110") (name "unconnected-(U1-HEADMIC_P-Pad113)") (class "Default")
      (node (ref "U1") (pin "113") (pinfunction "HEADMIC_P_113") (pintype "passive+no_connect"))
    )
    (net (code "111") (name "unconnected-(U1-HOST_RXD-Pad6)") (class "Default")
      (node (ref "U1") (pin "6") (pinfunction "HOST_RXD_6") (pintype "passive"))
    )
    (net (code "112") (name "unconnected-(U1-HOST_TXD-Pad5)") (class "Default")
      (node (ref "U1") (pin "5") (pinfunction "HOST_TXD_5") (pintype "passive"))
    )
    (net (code "113") (name "unconnected-(U1-HP_DET-Pad106)") (class "Default")
      (node (ref "U1") (pin "106") (pinfunction "HP_DET_106") (pintype "passive+no_connect"))
    )
    (net (code "114") (name "unconnected-(U1-HP_L-Pad112)") (class "Default")
      (node (ref "U1") (pin "112") (pinfunction "HP_L_112") (pintype "passive+no_connect"))
    )
    (net (code "115") (name "unconnected-(U1-HP_R-Pad103)") (class "Default")
      (node (ref "U1") (pin "103") (pinfunction "HP_R_103") (pintype "passive+no_connect"))
    )
    (net (code "116") (name "unconnected-(U1-KEYIN1-Pad91)") (class "Default")
      (node (ref "U1") (pin "91") (pinfunction "KEYIN1_91") (pintype "passive+no_connect"))
    )
    (net (code "117") (name "unconnected-(U1-KEYIN2-Pad92)") (class "Default")
      (node (ref "U1") (pin "92") (pinfunction "KEYIN2_92") (pintype "passive+no_connect"))
    )
    (net (code "118") (name "unconnected-(U1-KEYIN3-Pad93)") (class "Default")
      (node (ref "U1") (pin "93") (pinfunction "KEYIN3_93") (pintype "passive+no_connect"))
    )
    (net (code "119") (name "unconnected-(U1-KEYIN4-Pad94)") (class "Default")
      (node (ref "U1") (pin "94") (pinfunction "KEYIN4_94") (pintype "passive+no_connect"))
    )
    (net (code "120") (name "unconnected-(U1-KEYIN5-Pad95)") (class "Default")
      (node (ref "U1") (pin "95") (pinfunction "KEYIN5_95") (pintype "passive+no_connect"))
    )
    (net (code "121") (name "unconnected-(U1-KEYOUT0-Pad96)") (class "Default")
      (node (ref "U1") (pin "96") (pinfunction "KEYOUT0_96") (pintype "passive+no_connect"))
    )
    (net (code "122") (name "unconnected-(U1-KEYOUT1-Pad97)") (class "Default")
      (node (ref "U1") (pin "97") (pinfunction "KEYOUT1_97") (pintype "passive+no_connect"))
    )
    (net (code "123") (name "unconnected-(U1-KEYOUT2-Pad98)") (class "Default")
      (node (ref "U1") (pin "98") (pinfunction "KEYOUT2_98") (pintype "passive+no_connect"))
    )
    (net (code "124") (name "unconnected-(U1-KEYOUT3-Pad99)") (class "Default")
      (node (ref "U1") (pin "99") (pinfunction "KEYOUT3_99") (pintype "passive+no_connect"))
    )
    (net (code "125") (name "unconnected-(U1-LCD_FMARK-Pad42)") (class "Default")
      (node (ref "U1") (pin "42") (pinfunction "LCD_FMARK_42") (pintype "passive+no_connect"))
    )
    (net (code "126") (name "unconnected-(U1-NC-Pad73)") (class "Default")
      (node (ref "U1") (pin "73") (pinfunction "NC_73") (pintype "passive+no_connect"))
    )
    (net (code "127") (name "unconnected-(U1-RESERVED-Pad67)") (class "Default")
      (node (ref "U1") (pin "67") (pinfunction "RESERVED_67") (pintype "passive+no_connect"))
    )
    (net (code "128") (name "unconnected-(U1-RESERVED-Pad110)") (class "Default")
      (node (ref "U1") (pin "110") (pinfunction "RESERVED_110") (pintype "passive+no_connect"))
    )
    (net (code "129") (name "unconnected-(U1-RESERVED-Pad111)") (class "Default")
      (node (ref "U1") (pin "111") (pinfunction "RESERVED_111") (pintype "passive+no_connect"))
    )
    (net (code "130") (name "unconnected-(U1-RESERVED-Pad115)") (class "Default")
      (node (ref "U1") (pin "115") (pinfunction "RESERVED_115") (pintype "passive+no_connect"))
    )
    (net (code "131") (name "unconnected-(U1-SIM1_CLK{slash}GPIO_29-Pad69)") (class "Default")
      (node (ref "U1") (pin "69") (pinfunction "SIM1_CLK/GPIO_29_69") (pintype "passive+no_connect"))
    )
    (net (code "132") (name "unconnected-(U1-SIM1_DATA{slash}GPIO_30-Pad70)") (class "Default")
      (node (ref "U1") (pin "70") (pinfunction "SIM1_DATA/GPIO_30_70") (pintype "passive+no_connect"))
    )
    (net (code "133") (name "unconnected-(U1-SIM1_RST{slash}GPIO_31-Pad71)") (class "Default")
      (node (ref "U1") (pin "71") (pinfunction "SIM1_RST/GPIO_31_71") (pintype "passive+no_connect"))
    )
    (net (code "134") (name "unconnected-(U1-SIM1_VDD-Pad72)") (class "Default")
      (node (ref "U1") (pin "72") (pinfunction "SIM1_VDD_72") (pintype "passive+no_connect"))
    )
    (net (code "135") (name "unconnected-(U1-USIM_CD{slash}GPIO_23-Pad8)") (class "Default")
      (node (ref "U1") (pin "8") (pinfunction "USIM_CD/GPIO_23_8") (pintype "passive"))
    )
    (net (code "136") (name "unconnected-(U1-ZSP_UART_TXD{slash}GPIO_22-Pad7)") (class "Default")
      (node (ref "U1") (pin "7") (pinfunction "ZSP_UART_TXD/GPIO_22_7") (pintype "passive"))
    )
  )
)
